# cs301_Group_12.net
KiCad netlist of a schematic drawn in Altium Designer
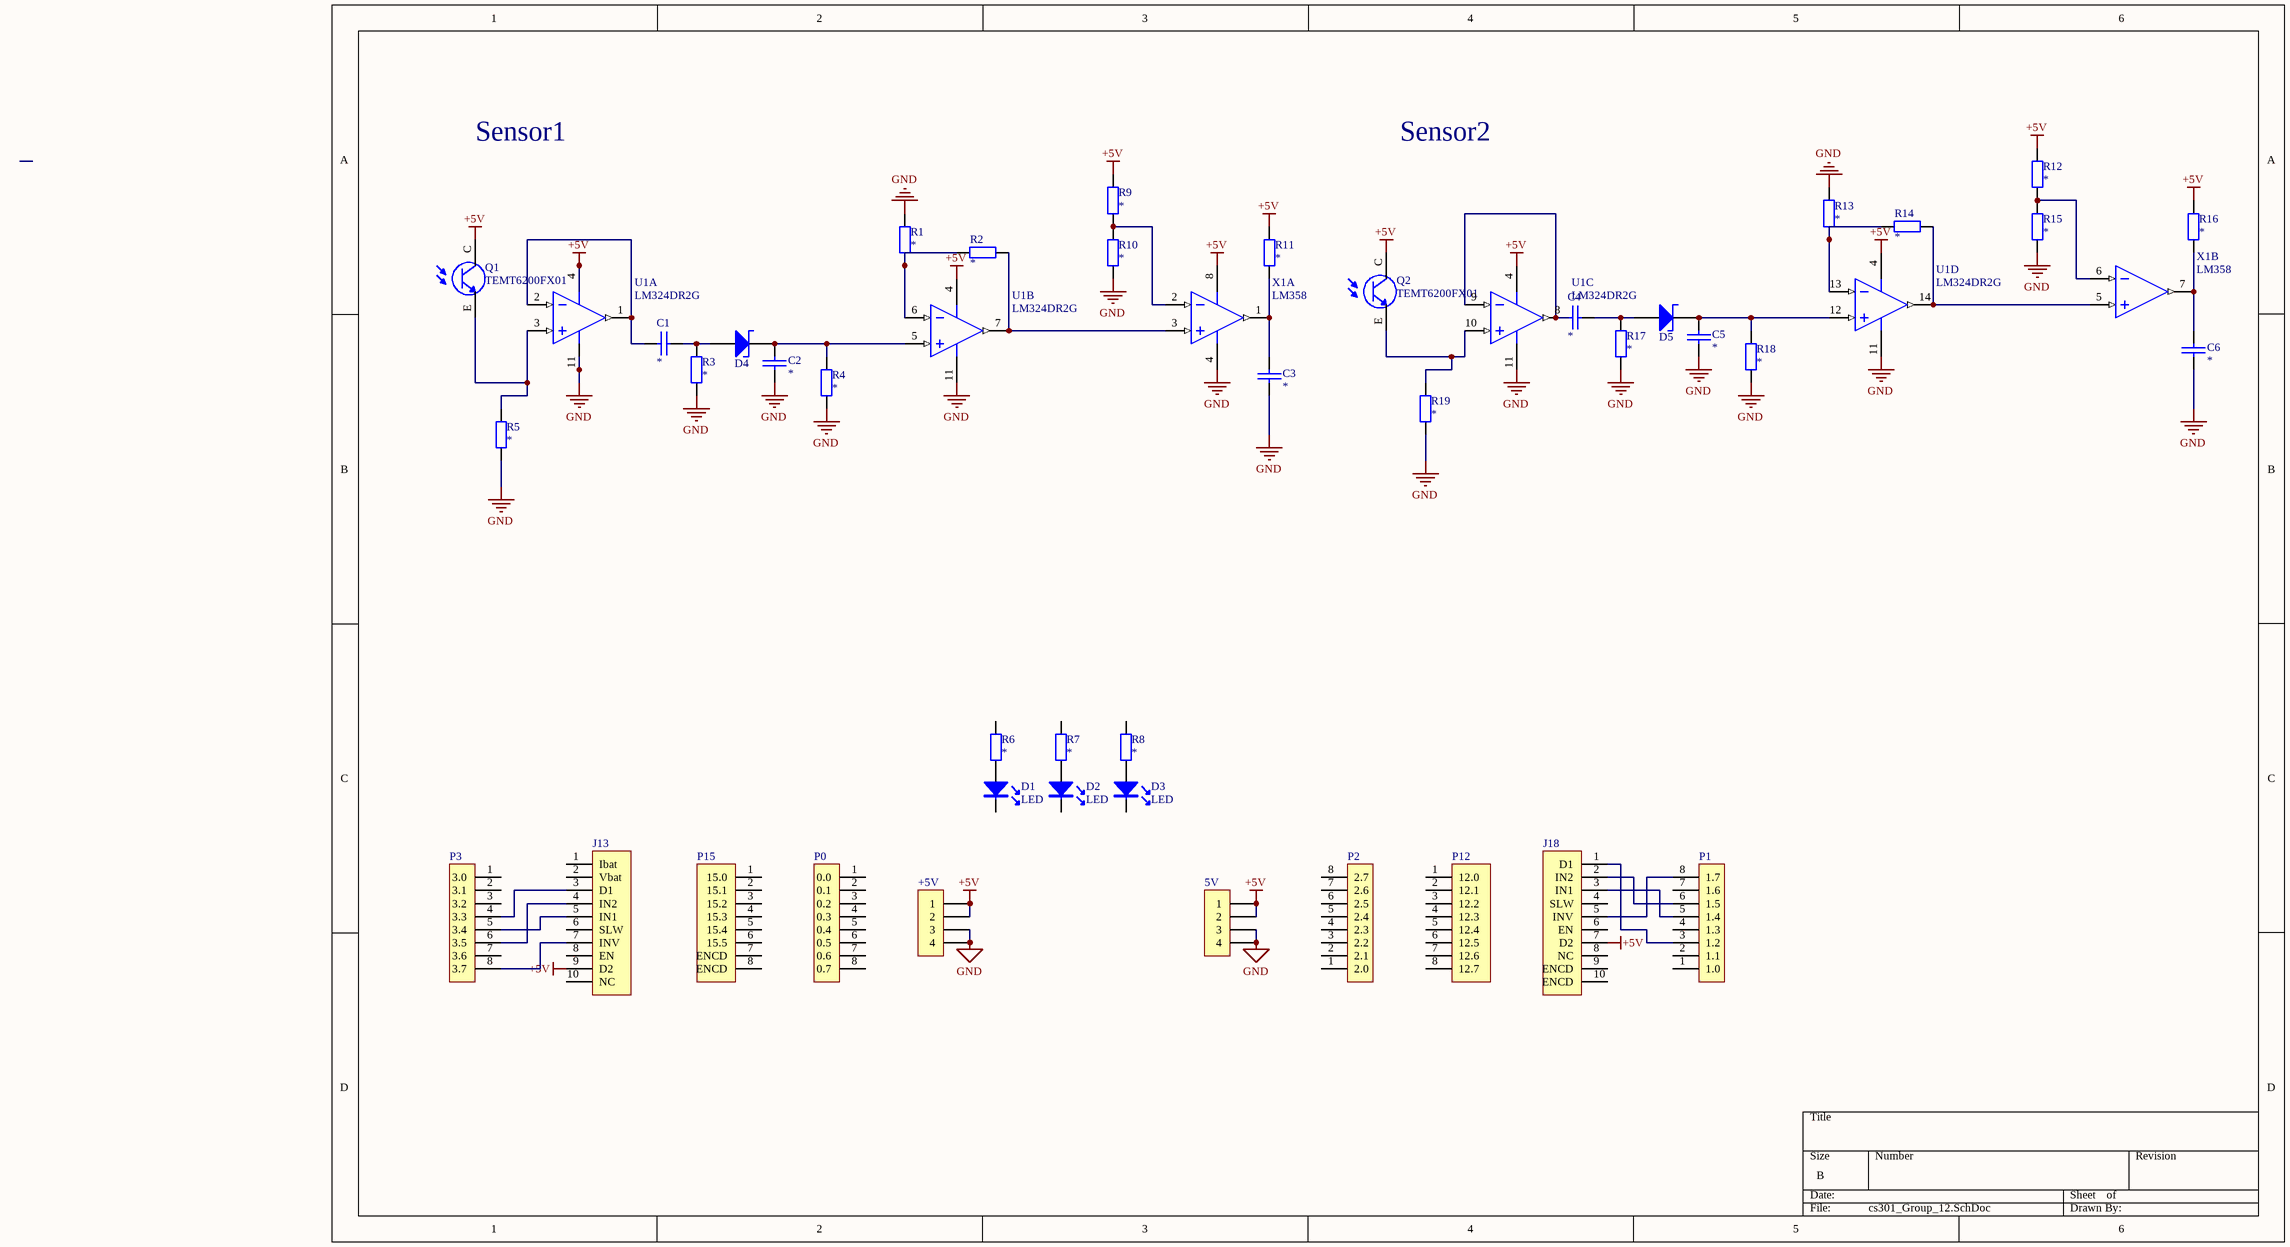
[diagram p0: cs301_Group_12.SchDoc]

(export (version "E")
  (design (tool "Eeschema 10.0.6"))
  (components
    (comp (ref "+5V")
      (value "5V")
      (footprint "IDC4")
      (description "Connector")
      (libsource (lib "Miscellaneous Devices") (part "CON4"))
    )
    (comp (ref "5V")
      (value "5V")
      (footprint "IDC4")
      (description "Connector")
      (libsource (lib "Miscellaneous Devices") (part "CON4"))
    )
    (comp (ref "C1")
      (value "*")
      (footprint "0805 CAP")
      (description "SMT ceramic capacitor 0805 size")
      (libsource (lib "EE209_Library") (part "CerCap_SMT_0805"))
    )
    (comp (ref "C2")
      (value "*")
      (footprint "0805 CAP")
      (description "SMT ceramic capacitor 0805 size")
      (libsource (lib "EE209_Library") (part "CerCap_SMT_0805"))
    )
    (comp (ref "C3")
      (value "*")
      (footprint "0805 CAP")
      (description "SMT ceramic capacitor 0805 size")
      (libsource (lib "EE209_Library") (part "CerCap_SMT_0805"))
    )
    (comp (ref "C4")
      (value "*")
      (footprint "0805 CAP")
      (description "SMT ceramic capacitor 0805 size")
      (libsource (lib "EE209_Library") (part "CerCap_SMT_0805"))
    )
    (comp (ref "C5")
      (value "*")
      (footprint "0805 CAP")
      (description "SMT ceramic capacitor 0805 size")
      (libsource (lib "EE209_Library") (part "CerCap_SMT_0805"))
    )
    (comp (ref "C6")
      (value "*")
      (footprint "0805 CAP")
      (description "SMT ceramic capacitor 0805 size")
      (libsource (lib "EE209_Library") (part "CerCap_SMT_0805"))
    )
    (comp (ref "D1") (value "LED") (footprint "LED0.1/5MM") (libsource (lib "COMSYS301_2013") (part "LED")))
    (comp (ref "D2") (value "LED") (footprint "LED0.1/5MM") (libsource (lib "COMSYS301_2013") (part "LED")))
    (comp (ref "D3") (value "LED") (footprint "LED0.1/5MM") (libsource (lib "COMSYS301_2013") (part "LED")))
    (comp (ref "D4")
      (value "BZT52H-B4V7")
      (footprint "SOD123")
      (description "SMT zener diode with SOD123 package")
      (fields
        (field (name "MANUFACTURER") "Nexperia USA Inc.")
        (field (name "MANUFACTURER PART NUMBER") "BZT52H-B4V7,115")
      )
      (libsource (lib "EE209_Library") (part "Zener_SMT_SOD123"))
    )
    (comp (ref "D5")
      (value "BZT52H-B4V7")
      (footprint "SOD123")
      (description "SMT zener diode with SOD123 package")
      (fields
        (field (name "MANUFACTURER") "Nexperia USA Inc.")
        (field (name "MANUFACTURER PART NUMBER") "BZT52H-B4V7,115")
      )
      (libsource (lib "EE209_Library") (part "Zener_SMT_SOD123"))
    )
    (comp (ref "J13")
      (value "CON10")
      (footprint "idc10")
      (description "Connector")
      (libsource (lib "Miscellaneous Devices") (part "CON10"))
    )
    (comp (ref "J18")
      (value "CON10")
      (footprint "IDC10")
      (description "Connector")
      (libsource (lib "") (part "CON10_1"))
    )
    (comp (ref "P0")
      (value "P0")
      (footprint "idc8")
      (description "Connector")
      (libsource (lib "") (part "CON8_1"))
    )
    (comp (ref "P1")
      (value "P1")
      (footprint "idc8")
      (description "Connector")
      (libsource (lib "Miscellaneous Devices") (part "CON8"))
    )
    (comp (ref "P2")
      (value "P2")
      (footprint "idc8")
      (description "Connector")
      (libsource (lib "") (part "CON8_2"))
    )
    (comp (ref "P3")
      (value "P3")
      (footprint "idc8")
      (description "Connector")
      (libsource (lib "") (part "CON8_1"))
    )
    (comp (ref "P12")
      (value "P12")
      (footprint "idc8")
      (description "Connector")
      (libsource (lib "") (part "CON8_1_1"))
    )
    (comp (ref "P15")
      (value "P15")
      (footprint "idc8")
      (description "Connector")
      (libsource (lib "Miscellaneous Devices") (part "CON8_1"))
    )
    (comp (ref "Q1")
      (value "TEMT6200FX01")
      (footprint "XDCR_TEMT6200FX01")
      (description "Phototransistors 550nm Top View 0805 (2012 Metric)")
      (fields (field (name "MF") "Vishay Semiconductor"))
      (libsource (lib "TEMT6200FX01") (part "TEMT6200FX01"))
    )
    (comp (ref "Q2")
      (value "TEMT6200FX01")
      (footprint "XDCR_TEMT6200FX01")
      (description "Phototransistors 550nm Top View 0805 (2012 Metric)")
      (fields (field (name "MF") "Vishay Semiconductor"))
      (libsource (lib "TEMT6200FX01") (part "TEMT6200FX01"))
    )
    (comp (ref "R1")
      (value "*")
      (footprint "0805 RES")
      (description "0805 resistor")
      (fields (field (name "PUBLISHER") "Altium Limited"))
      (libsource (lib "") (part "Res_SMT_0805_2"))
    )
    (comp (ref "R2")
      (value "*")
      (footprint "0805 RES")
      (description "0805 resistor")
      (fields (field (name "PUBLISHER") "Altium Limited"))
      (libsource (lib "EE209_Library") (part "Res_SMT_0805"))
    )
    (comp (ref "R3")
      (value "*")
      (footprint "0805 RES")
      (description "0805 resistor")
      (fields (field (name "PUBLISHER") "Altium Limited"))
      (libsource (lib "") (part "Res_SMT_0805_2"))
    )
    (comp (ref "R4")
      (value "*")
      (footprint "0805 RES")
      (description "0805 resistor")
      (fields (field (name "PUBLISHER") "Altium Limited"))
      (libsource (lib "") (part "Res_SMT_0805_2"))
    )
    (comp (ref "R5")
      (value "*")
      (footprint "0805 RES")
      (description "0805 resistor")
      (fields (field (name "PUBLISHER") "Altium Limited"))
      (libsource (lib "") (part "Res_SMT_0805_2"))
    )
    (comp (ref "R6")
      (value "*")
      (footprint "0805 RES")
      (description "0805 resistor")
      (fields (field (name "PUBLISHER") "Altium Limited"))
      (libsource (lib "") (part "Res_SMT_0805_2"))
    )
    (comp (ref "R7")
      (value "*")
      (footprint "0805 RES")
      (description "0805 resistor")
      (fields (field (name "PUBLISHER") "Altium Limited"))
      (libsource (lib "") (part "Res_SMT_0805_2"))
    )
    (comp (ref "R8")
      (value "*")
      (footprint "0805 RES")
      (description "0805 resistor")
      (fields (field (name "PUBLISHER") "Altium Limited"))
      (libsource (lib "") (part "Res_SMT_0805_2"))
    )
    (comp (ref "R9")
      (value "*")
      (footprint "0805 RES")
      (description "0805 resistor")
      (fields (field (name "PUBLISHER") "Altium Limited"))
      (libsource (lib "") (part "Res_SMT_0805_1"))
    )
    (comp (ref "R10")
      (value "*")
      (footprint "0805 RES")
      (description "0805 resistor")
      (fields (field (name "PUBLISHER") "Altium Limited"))
      (libsource (lib "") (part "Res_SMT_0805_1"))
    )
    (comp (ref "R11")
      (value "*")
      (footprint "0805 RES")
      (description "0805 resistor")
      (fields (field (name "PUBLISHER") "Altium Limited"))
      (libsource (lib "") (part "Res_SMT_0805_1"))
    )
    (comp (ref "R12")
      (value "*")
      (footprint "0805 RES")
      (description "0805 resistor")
      (fields (field (name "PUBLISHER") "Altium Limited"))
      (libsource (lib "") (part "Res_SMT_0805_1"))
    )
    (comp (ref "R13")
      (value "*")
      (footprint "0805 RES")
      (description "0805 resistor")
      (fields (field (name "PUBLISHER") "Altium Limited"))
      (libsource (lib "") (part "Res_SMT_0805_2"))
    )
    (comp (ref "R14")
      (value "*")
      (footprint "0805 RES")
      (description "0805 resistor")
      (fields (field (name "PUBLISHER") "Altium Limited"))
      (libsource (lib "EE209_Library") (part "Res_SMT_0805"))
    )
    (comp (ref "R15")
      (value "*")
      (footprint "0805 RES")
      (description "0805 resistor")
      (fields (field (name "PUBLISHER") "Altium Limited"))
      (libsource (lib "") (part "Res_SMT_0805_1"))
    )
    (comp (ref "R16")
      (value "*")
      (footprint "0805 RES")
      (description "0805 resistor")
      (fields (field (name "PUBLISHER") "Altium Limited"))
      (libsource (lib "") (part "Res_SMT_0805_1"))
    )
    (comp (ref "R17")
      (value "*")
      (footprint "0805 RES")
      (description "0805 resistor")
      (fields (field (name "PUBLISHER") "Altium Limited"))
      (libsource (lib "") (part "Res_SMT_0805_2"))
    )
    (comp (ref "R18")
      (value "*")
      (footprint "0805 RES")
      (description "0805 resistor")
      (fields (field (name "PUBLISHER") "Altium Limited"))
      (libsource (lib "") (part "Res_SMT_0805_2"))
    )
    (comp (ref "R19")
      (value "*")
      (footprint "0805 RES")
      (description "0805 resistor")
      (fields (field (name "PUBLISHER") "Altium Limited"))
      (libsource (lib "") (part "Res_SMT_0805_2"))
    )
    (comp (ref "U1")
      (value "LM324DR2G")
      (footprint "SOIC-14")
      (fields (field (name "MANUFACTURER") "On Semiconductor"))
      (libsource (lib "EE209_Library") (part "LM324DR_SMT_SOIC16"))
    )
    (comp (ref "X1")
      (value "LM358")
      (footprint "SO - 8")
      (description "IC OPAMP 8SOIC")
      (libsource (lib "EE209_Library") (part "LM358_SMT_SOIC8"))
    )
  )
  (nets
    (net (code "1") (name "+5V") (class "Default")
      (node (ref "+5V") (pin "1") (pinfunction "1_1") (pintype "passive"))
      (node (ref "+5V") (pin "2") (pinfunction "2_2") (pintype "passive"))
      (node (ref "5V") (pin "1") (pinfunction "1_1") (pintype "passive"))
      (node (ref "5V") (pin "2") (pinfunction "2_2") (pintype "passive"))
      (node (ref "J13") (pin "9") (pinfunction "D2_9") (pintype "passive"))
      (node (ref "J18") (pin "7") (pinfunction "D2_7") (pintype "passive"))
      (node (ref "Q1") (pin "C") (pinfunction "C_C") (pintype "passive"))
      (node (ref "Q2") (pin "C") (pinfunction "C_C") (pintype "passive"))
      (node (ref "R11") (pin "1") (pinfunction "1_1") (pintype "passive"))
      (node (ref "R12") (pin "1") (pinfunction "1_1") (pintype "passive"))
      (node (ref "R16") (pin "1") (pinfunction "1_1") (pintype "passive"))
      (node (ref "R9") (pin "1") (pinfunction "1_1") (pintype "passive"))
      (node (ref "U1") (pin "4") (pinfunction "VCC_4") (pintype "power_in"))
      (node (ref "X1") (pin "8") (pinfunction "VDD_8") (pintype "power_in"))
    )
    (net (code "2") (name "GND") (class "Default")
      (node (ref "+5V") (pin "3") (pinfunction "3_3") (pintype "passive"))
      (node (ref "+5V") (pin "4") (pinfunction "4_4") (pintype "passive"))
      (node (ref "5V") (pin "3") (pinfunction "3_3") (pintype "passive"))
      (node (ref "5V") (pin "4") (pinfunction "4_4") (pintype "passive"))
      (node (ref "C2") (pin "2") (pinfunction "2_2") (pintype "passive"))
      (node (ref "C3") (pin "2") (pinfunction "2_2") (pintype "passive"))
      (node (ref "C5") (pin "2") (pinfunction "2_2") (pintype "passive"))
      (node (ref "C6") (pin "2") (pinfunction "2_2") (pintype "passive"))
      (node (ref "R1") (pin "2") (pinfunction "2_2") (pintype "passive"))
      (node (ref "R10") (pin "2") (pinfunction "2_2") (pintype "passive"))
      (node (ref "R13") (pin "2") (pinfunction "2_2") (pintype "passive"))
      (node (ref "R15") (pin "2") (pinfunction "2_2") (pintype "passive"))
      (node (ref "R17") (pin "1") (pinfunction "1_1") (pintype "passive"))
      (node (ref "R18") (pin "1") (pinfunction "1_1") (pintype "passive"))
      (node (ref "R19") (pin "1") (pinfunction "1_1") (pintype "passive"))
      (node (ref "R3") (pin "1") (pinfunction "1_1") (pintype "passive"))
      (node (ref "R4") (pin "1") (pinfunction "1_1") (pintype "passive"))
      (node (ref "R5") (pin "1") (pinfunction "1_1") (pintype "passive"))
      (node (ref "U1") (pin "11") (pinfunction "VEE/GND_11") (pintype "power_in"))
      (node (ref "X1") (pin "4") (pinfunction "VSS_4") (pintype "power_in"))
    )
    (net (code "3") (name "Net-(D1-1)") (class "Default")
      (node (ref "D1") (pin "A") (pinfunction "1_A") (pintype "passive"))
      (node (ref "R6") (pin "1") (pinfunction "1_1") (pintype "passive"))
    )
    (net (code "4") (name "Net-(D2-1)") (class "Default")
      (node (ref "D2") (pin "A") (pinfunction "1_A") (pintype "passive"))
      (node (ref "R7") (pin "1") (pinfunction "1_1") (pintype "passive"))
    )
    (net (code "5") (name "Net-(D3-1)") (class "Default")
      (node (ref "D3") (pin "A") (pinfunction "1_A") (pintype "passive"))
      (node (ref "R8") (pin "1") (pinfunction "1_1") (pintype "passive"))
    )
    (net (code "6") (name "Net-(D4-A)") (class "Default")
      (node (ref "C1") (pin "2") (pinfunction "2_2") (pintype "passive"))
      (node (ref "D4") (pin "1") (pinfunction "A_1") (pintype "passive"))
      (node (ref "R3") (pin "2") (pinfunction "2_2") (pintype "passive"))
    )
    (net (code "7") (name "Net-(D4-K)") (class "Default")
      (node (ref "C2") (pin "1") (pinfunction "1_1") (pintype "passive"))
      (node (ref "D4") (pin "2") (pinfunction "K_2") (pintype "passive"))
      (node (ref "R4") (pin "2") (pinfunction "2_2") (pintype "passive"))
      (node (ref "U1") (pin "5") (pinfunction "IN2+_5") (pintype "input"))
    )
    (net (code "8") (name "Net-(D5-A)") (class "Default")
      (node (ref "C4") (pin "2") (pinfunction "2_2") (pintype "passive"))
      (node (ref "D5") (pin "1") (pinfunction "A_1") (pintype "passive"))
      (node (ref "R17") (pin "2") (pinfunction "2_2") (pintype "passive"))
    )
    (net (code "9") (name "Net-(D5-K)") (class "Default")
      (node (ref "C5") (pin "1") (pinfunction "1_1") (pintype "passive"))
      (node (ref "D5") (pin "2") (pinfunction "K_2") (pintype "passive"))
      (node (ref "R18") (pin "2") (pinfunction "2_2") (pintype "passive"))
      (node (ref "U1") (pin "12") (pinfunction "IN4+_12") (pintype "input"))
    )
    (net (code "10") (name "Net-(J13-D1)") (class "Default")
      (node (ref "J13") (pin "3") (pinfunction "D1_3") (pintype "passive"))
      (node (ref "P3") (pin "4") (pinfunction "0.3_4") (pintype "passive"))
    )
    (net (code "11") (name "Net-(J13-IN1)") (class "Default")
      (node (ref "J13") (pin "5") (pinfunction "IN1_5") (pintype "passive"))
      (node (ref "P3") (pin "5") (pinfunction "0.4_5") (pintype "passive"))
    )
    (net (code "12") (name "Net-(J13-IN2)") (class "Default")
      (node (ref "J13") (pin "4") (pinfunction "IN2_4") (pintype "passive"))
      (node (ref "P3") (pin "6") (pinfunction "0.5_6") (pintype "passive"))
    )
    (net (code "13") (name "Net-(J13-INV)") (class "Default")
      (node (ref "J13") (pin "7") (pinfunction "INV_7") (pintype "passive"))
      (node (ref "P3") (pin "8") (pinfunction "0.7_8") (pintype "passive"))
    )
    (net (code "14") (name "Net-(J18-D1)") (class "Default")
      (node (ref "J18") (pin "1") (pinfunction "D1_1") (pintype "passive"))
      (node (ref "P1") (pin "3") (pinfunction "1.2_3") (pintype "passive"))
    )
    (net (code "15") (name "Net-(J18-IN1)") (class "Default")
      (node (ref "J18") (pin "3") (pinfunction "IN1_3") (pintype "passive"))
      (node (ref "P1") (pin "5") (pinfunction "1.4_5") (pintype "passive"))
    )
    (net (code "16") (name "Net-(J18-IN2)") (class "Default")
      (node (ref "J18") (pin "2") (pinfunction "IN2_2") (pintype "passive"))
      (node (ref "P1") (pin "6") (pinfunction "1.5_6") (pintype "passive"))
    )
    (net (code "17") (name "Net-(J18-INV)") (class "Default")
      (node (ref "J18") (pin "5") (pinfunction "INV_5") (pintype "passive"))
      (node (ref "P1") (pin "8") (pinfunction "1.7_8") (pintype "passive"))
    )
    (net (code "18") (name "Net-(U1A-IN1+)") (class "Default")
      (node (ref "Q1") (pin "E") (pinfunction "E_E") (pintype "passive"))
      (node (ref "R5") (pin "2") (pinfunction "2_2") (pintype "passive"))
      (node (ref "U1") (pin "3") (pinfunction "IN1+_3") (pintype "input"))
    )
    (net (code "19") (name "Net-(U1A-IN1-)") (class "Default")
      (node (ref "C1") (pin "1") (pinfunction "1_1") (pintype "passive"))
      (node (ref "U1") (pin "1") (pinfunction "OUT1_1") (pintype "output"))
      (node (ref "U1") (pin "2") (pinfunction "IN1-_2") (pintype "input"))
    )
    (net (code "20") (name "Net-(U1B-IN2-)") (class "Default")
      (node (ref "R1") (pin "1") (pinfunction "1_1") (pintype "passive"))
      (node (ref "R2") (pin "2") (pinfunction "2_2") (pintype "passive"))
      (node (ref "U1") (pin "6") (pinfunction "IN2-_6") (pintype "input"))
    )
    (net (code "21") (name "Net-(U1B-OUT2)") (class "Default")
      (node (ref "R2") (pin "1") (pinfunction "1_1") (pintype "passive"))
      (node (ref "U1") (pin "7") (pinfunction "OUT2_7") (pintype "output"))
      (node (ref "X1") (pin "3") (pinfunction "VINA+_3") (pintype "input"))
    )
    (net (code "22") (name "Net-(U1C-IN3+)") (class "Default")
      (node (ref "Q2") (pin "E") (pinfunction "E_E") (pintype "passive"))
      (node (ref "R19") (pin "2") (pinfunction "2_2") (pintype "passive"))
      (node (ref "U1") (pin "10") (pinfunction "IN3+_10") (pintype "input"))
    )
    (net (code "23") (name "Net-(U1C-IN3-)") (class "Default")
      (node (ref "C4") (pin "1") (pinfunction "1_1") (pintype "passive"))
      (node (ref "U1") (pin "8") (pinfunction "OUT3_8") (pintype "output"))
      (node (ref "U1") (pin "9") (pinfunction "IN3-_9") (pintype "input"))
    )
    (net (code "24") (name "Net-(U1D-IN4-)") (class "Default")
      (node (ref "R13") (pin "1") (pinfunction "1_1") (pintype "passive"))
      (node (ref "R14") (pin "2") (pinfunction "2_2") (pintype "passive"))
      (node (ref "U1") (pin "13") (pinfunction "IN4-_13") (pintype "input"))
    )
    (net (code "25") (name "Net-(U1D-OUT4)") (class "Default")
      (node (ref "R14") (pin "1") (pinfunction "1_1") (pintype "passive"))
      (node (ref "U1") (pin "14") (pinfunction "OUT4_14") (pintype "output"))
      (node (ref "X1") (pin "5") (pinfunction "VINA+_5") (pintype "input"))
    )
    (net (code "26") (name "Net-(X1A-VINA-)") (class "Default")
      (node (ref "R10") (pin "1") (pinfunction "1_1") (pintype "passive"))
      (node (ref "R9") (pin "2") (pinfunction "2_2") (pintype "passive"))
      (node (ref "X1") (pin "2") (pinfunction "VINA-_2") (pintype "input"))
    )
    (net (code "27") (name "Net-(X1A-VOUTA)") (class "Default")
      (node (ref "C3") (pin "1") (pinfunction "1_1") (pintype "passive"))
      (node (ref "R11") (pin "2") (pinfunction "2_2") (pintype "passive"))
      (node (ref "X1") (pin "1") (pinfunction "VOUTA_1") (pintype "output"))
    )
    (net (code "28") (name "Net-(X1B-VINA-)") (class "Default")
      (node (ref "R12") (pin "2") (pinfunction "2_2") (pintype "passive"))
      (node (ref "R15") (pin "1") (pinfunction "1_1") (pintype "passive"))
      (node (ref "X1") (pin "6") (pinfunction "VINA-_6") (pintype "input"))
    )
    (net (code "29") (name "Net-(X1B-VOUTA)") (class "Default")
      (node (ref "C6") (pin "1") (pinfunction "1_1") (pintype "passive"))
      (node (ref "R16") (pin "2") (pinfunction "2_2") (pintype "passive"))
      (node (ref "X1") (pin "7") (pinfunction "VOUTA_7") (pintype "output"))
    )
    (net (code "30") (name "unconnected-(D1-2-PadK)") (class "Default")
      (node (ref "D1") (pin "K") (pinfunction "2_K") (pintype "passive"))
    )
    (net (code "31") (name "unconnected-(D2-2-PadK)") (class "Default")
      (node (ref "D2") (pin "K") (pinfunction "2_K") (pintype "passive"))
    )
    (net (code "32") (name "unconnected-(D3-2-PadK)") (class "Default")
      (node (ref "D3") (pin "K") (pinfunction "2_K") (pintype "passive"))
    )
    (net (code "33") (name "unconnected-(J13-EN-Pad8)") (class "Default")
      (node (ref "J13") (pin "8") (pinfunction "EN_8") (pintype "passive"))
    )
    (net (code "34") (name "unconnected-(J13-Ibat-Pad1)") (class "Default")
      (node (ref "J13") (pin "1") (pinfunction "Ibat_1") (pintype "passive"))
    )
    (net (code "35") (name "unconnected-(J13-NC-Pad10)") (class "Default")
      (node (ref "J13") (pin "10") (pinfunction "NC_10") (pintype "passive"))
    )
    (net (code "36") (name "unconnected-(J13-SLW-Pad6)") (class "Default")
      (node (ref "J13") (pin "6") (pinfunction "SLW_6") (pintype "passive"))
    )
    (net (code "37") (name "unconnected-(J13-Vbat-Pad2)") (class "Default")
      (node (ref "J13") (pin "2") (pinfunction "Vbat_2") (pintype "passive"))
    )
    (net (code "38") (name "unconnected-(J18-EN-Pad6)") (class "Default")
      (node (ref "J18") (pin "6") (pinfunction "EN_6") (pintype "passive"))
    )
    (net (code "39") (name "unconnected-(J18-ENCD-Pad9)") (class "Default")
      (node (ref "J18") (pin "9") (pinfunction "ENCD_9") (pintype "passive"))
    )
    (net (code "40") (name "unconnected-(J18-ENCD-Pad10)") (class "Default")
      (node (ref "J18") (pin "10") (pinfunction "ENCD_10") (pintype "passive"))
    )
    (net (code "41") (name "unconnected-(J18-NC-Pad8)") (class "Default")
      (node (ref "J18") (pin "8") (pinfunction "NC_8") (pintype "passive"))
    )
    (net (code "42") (name "unconnected-(J18-SLW-Pad4)") (class "Default")
      (node (ref "J18") (pin "4") (pinfunction "SLW_4") (pintype "passive"))
    )
    (net (code "43") (name "unconnected-(P0-0.0-Pad1)") (class "Default")
      (node (ref "P0") (pin "1") (pinfunction "0.0_1") (pintype "passive"))
    )
    (net (code "44") (name "unconnected-(P0-0.1-Pad2)") (class "Default")
      (node (ref "P0") (pin "2") (pinfunction "0.1_2") (pintype "passive"))
    )
    (net (code "45") (name "unconnected-(P0-0.2-Pad3)") (class "Default")
      (node (ref "P0") (pin "3") (pinfunction "0.2_3") (pintype "passive"))
    )
    (net (code "46") (name "unconnected-(P0-0.3-Pad4)") (class "Default")
      (node (ref "P0") (pin "4") (pinfunction "0.3_4") (pintype "passive"))
    )
    (net (code "47") (name "unconnected-(P0-0.4-Pad5)") (class "Default")
      (node (ref "P0") (pin "5") (pinfunction "0.4_5") (pintype "passive"))
    )
    (net (code "48") (name "unconnected-(P0-0.5-Pad6)") (class "Default")
      (node (ref "P0") (pin "6") (pinfunction "0.5_6") (pintype "passive"))
    )
    (net (code "49") (name "unconnected-(P0-0.6-Pad7)") (class "Default")
      (node (ref "P0") (pin "7") (pinfunction "0.6_7") (pintype "passive"))
    )
    (net (code "50") (name "unconnected-(P0-0.7-Pad8)") (class "Default")
      (node (ref "P0") (pin "8") (pinfunction "0.7_8") (pintype "passive"))
    )
    (net (code "51") (name "unconnected-(P1-1.0-Pad1)") (class "Default")
      (node (ref "P1") (pin "1") (pinfunction "1.0_1") (pintype "passive"))
    )
    (net (code "52") (name "unconnected-(P1-1.1-Pad2)") (class "Default")
      (node (ref "P1") (pin "2") (pinfunction "1.1_2") (pintype "passive"))
    )
    (net (code "53") (name "unconnected-(P1-1.3-Pad4)") (class "Default")
      (node (ref "P1") (pin "4") (pinfunction "1.3_4") (pintype "passive"))
    )
    (net (code "54") (name "unconnected-(P1-1.6-Pad7)") (class "Default")
      (node (ref "P1") (pin "7") (pinfunction "1.6_7") (pintype "passive"))
    )
    (net (code "55") (name "unconnected-(P2-2.0-Pad1)") (class "Default")
      (node (ref "P2") (pin "1") (pinfunction "2.0_1") (pintype "passive"))
    )
    (net (code "56") (name "unconnected-(P2-2.1-Pad2)") (class "Default")
      (node (ref "P2") (pin "2") (pinfunction "2.1_2") (pintype "passive"))
    )
    (net (code "57") (name "unconnected-(P2-2.2-Pad3)") (class "Default")
      (node (ref "P2") (pin "3") (pinfunction "2.2_3") (pintype "passive"))
    )
    (net (code "58") (name "unconnected-(P2-2.3-Pad4)") (class "Default")
      (node (ref "P2") (pin "4") (pinfunction "2.3_4") (pintype "passive"))
    )
    (net (code "59") (name "unconnected-(P2-2.4-Pad5)") (class "Default")
      (node (ref "P2") (pin "5") (pinfunction "2.4_5") (pintype "passive"))
    )
    (net (code "60") (name "unconnected-(P2-2.5-Pad6)") (class "Default")
      (node (ref "P2") (pin "6") (pinfunction "2.5_6") (pintype "passive"))
    )
    (net (code "61") (name "unconnected-(P2-2.6-Pad7)") (class "Default")
      (node (ref "P2") (pin "7") (pinfunction "2.6_7") (pintype "passive"))
    )
    (net (code "62") (name "unconnected-(P2-2.7-Pad8)") (class "Default")
      (node (ref "P2") (pin "8") (pinfunction "2.7_8") (pintype "passive"))
    )
    (net (code "63") (name "unconnected-(P3-0.0-Pad1)") (class "Default")
      (node (ref "P3") (pin "1") (pinfunction "0.0_1") (pintype "passive"))
    )
    (net (code "64") (name "unconnected-(P3-0.1-Pad2)") (class "Default")
      (node (ref "P3") (pin "2") (pinfunction "0.1_2") (pintype "passive"))
    )
    (net (code "65") (name "unconnected-(P3-0.2-Pad3)") (class "Default")
      (node (ref "P3") (pin "3") (pinfunction "0.2_3") (pintype "passive"))
    )
    (net (code "66") (name "unconnected-(P3-0.6-Pad7)") (class "Default")
      (node (ref "P3") (pin "7") (pinfunction "0.6_7") (pintype "passive"))
    )
    (net (code "67") (name "unconnected-(P12-12.0-Pad1)") (class "Default")
      (node (ref "P12") (pin "1") (pinfunction "12.0_1") (pintype "passive"))
    )
    (net (code "68") (name "unconnected-(P12-12.1-Pad2)") (class "Default")
      (node (ref "P12") (pin "2") (pinfunction "12.1_2") (pintype "passive"))
    )
    (net (code "69") (name "unconnected-(P12-12.2-Pad3)") (class "Default")
      (node (ref "P12") (pin "3") (pinfunction "12.2_3") (pintype "passive"))
    )
    (net (code "70") (name "unconnected-(P12-12.3-Pad4)") (class "Default")
      (node (ref "P12") (pin "4") (pinfunction "12.3_4") (pintype "passive"))
    )
    (net (code "71") (name "unconnected-(P12-12.4-Pad5)") (class "Default")
      (node (ref "P12") (pin "5") (pinfunction "12.4_5") (pintype "passive"))
    )
    (net (code "72") (name "unconnected-(P12-12.5-Pad6)") (class "Default")
      (node (ref "P12") (pin "6") (pinfunction "12.5_6") (pintype "passive"))
    )
    (net (code "73") (name "unconnected-(P12-12.6-Pad7)") (class "Default")
      (node (ref "P12") (pin "7") (pinfunction "12.6_7") (pintype "passive"))
    )
    (net (code "74") (name "unconnected-(P12-12.7-Pad8)") (class "Default")
      (node (ref "P12") (pin "8") (pinfunction "12.7_8") (pintype "passive"))
    )
    (net (code "75") (name "unconnected-(P15-15.0-Pad1)") (class "Default")
      (node (ref "P15") (pin "1") (pinfunction "15.0_1") (pintype "passive"))
    )
    (net (code "76") (name "unconnected-(P15-15.1-Pad2)") (class "Default")
      (node (ref "P15") (pin "2") (pinfunction "15.1_2") (pintype "passive"))
    )
    (net (code "77") (name "unconnected-(P15-15.2-Pad3)") (class "Default")
      (node (ref "P15") (pin "3") (pinfunction "15.2_3") (pintype "passive"))
    )
    (net (code "78") (name "unconnected-(P15-15.3-Pad4)") (class "Default")
      (node (ref "P15") (pin "4") (pinfunction "15.3_4") (pintype "passive"))
    )
    (net (code "79") (name "unconnected-(P15-15.4-Pad5)") (class "Default")
      (node (ref "P15") (pin "5") (pinfunction "15.4_5") (pintype "passive"))
    )
    (net (code "80") (name "unconnected-(P15-15.5-Pad6)") (class "Default")
      (node (ref "P15") (pin "6") (pinfunction "15.5_6") (pintype "passive"))
    )
    (net (code "81") (name "unconnected-(P15-ENCD-Pad7)") (class "Default")
      (node (ref "P15") (pin "7") (pinfunction "ENCD_7") (pintype "passive"))
    )
    (net (code "82") (name "unconnected-(P15-ENCD-Pad8)") (class "Default")
      (node (ref "P15") (pin "8") (pinfunction "ENCD_8") (pintype "passive"))
    )
    (net (code "83") (name "unconnected-(R6-Pad2)") (class "Default")
      (node (ref "R6") (pin "2") (pinfunction "2_2") (pintype "passive"))
    )
    (net (code "84") (name "unconnected-(R7-Pad2)") (class "Default")
      (node (ref "R7") (pin "2") (pinfunction "2_2") (pintype "passive"))
    )
    (net (code "85") (name "unconnected-(R8-Pad2)") (class "Default")
      (node (ref "R8") (pin "2") (pinfunction "2_2") (pintype "passive"))
    )
  )
)
